# E3.net
KiCad netlist of a schematic drawn in Altium Designer
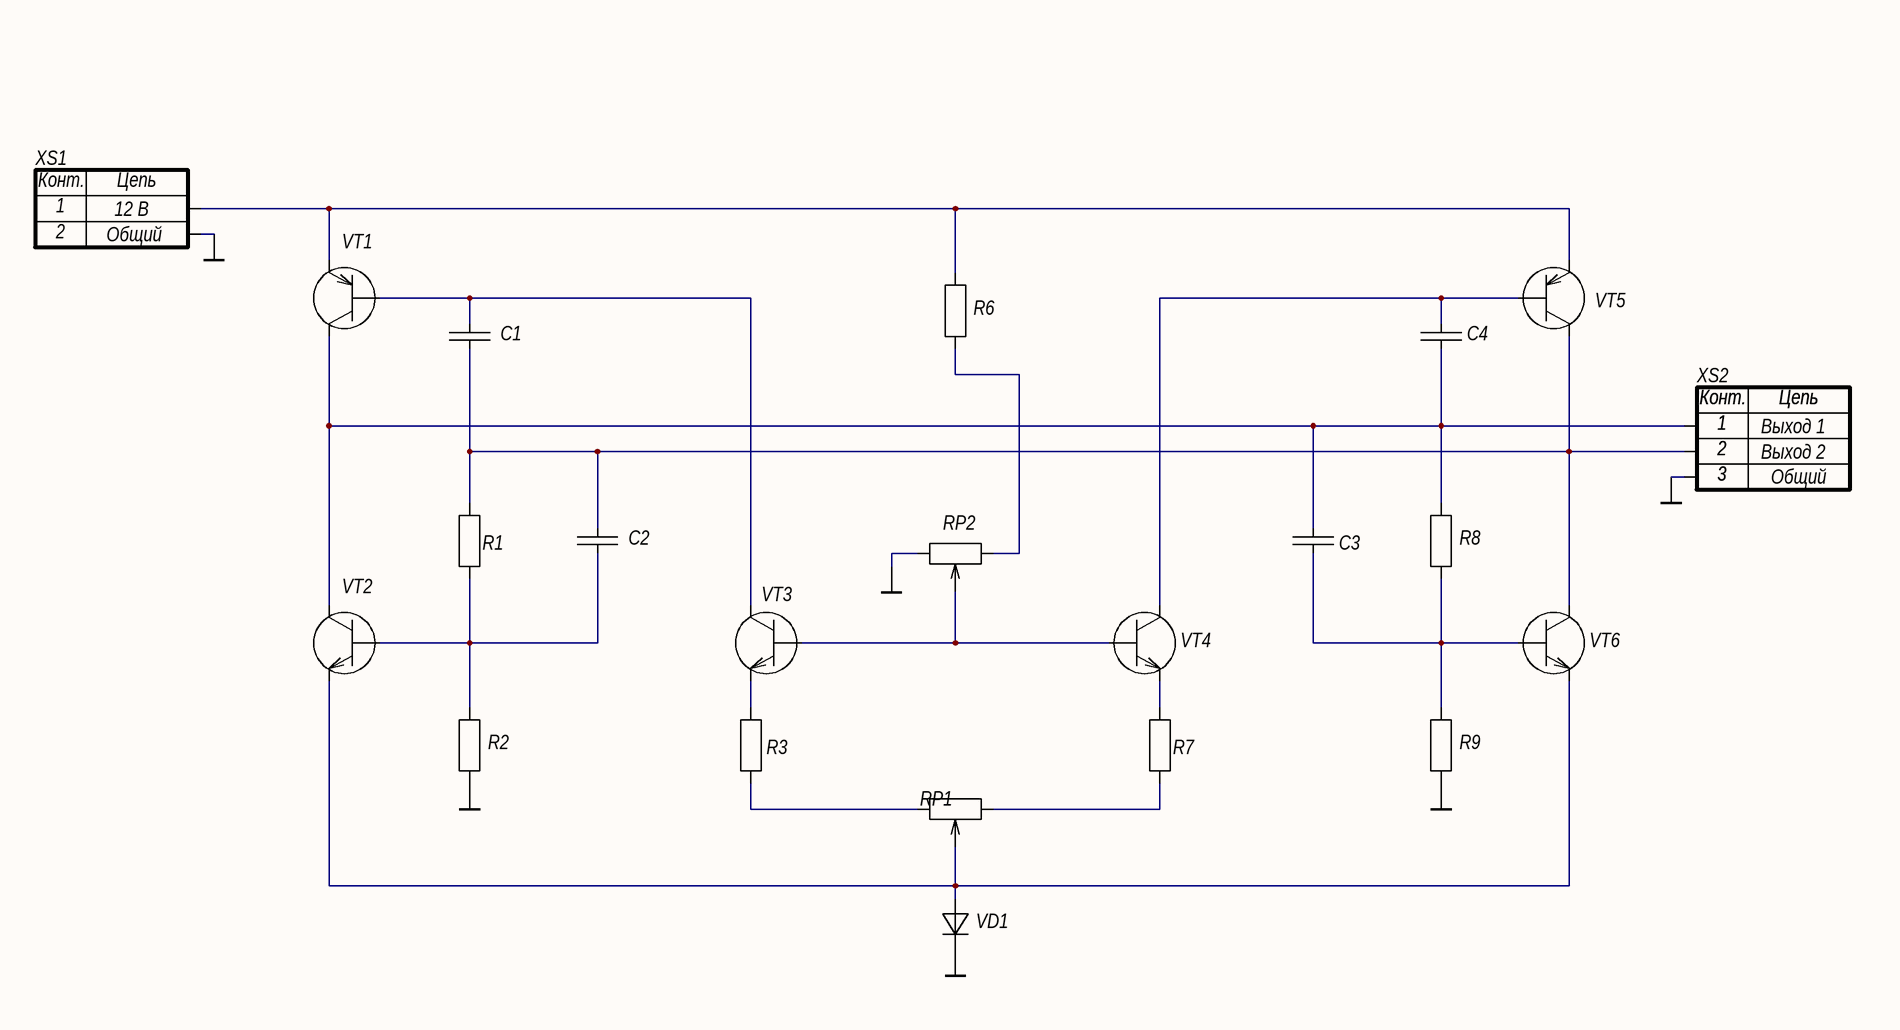
[diagram p0: E3.SchDoc, left]
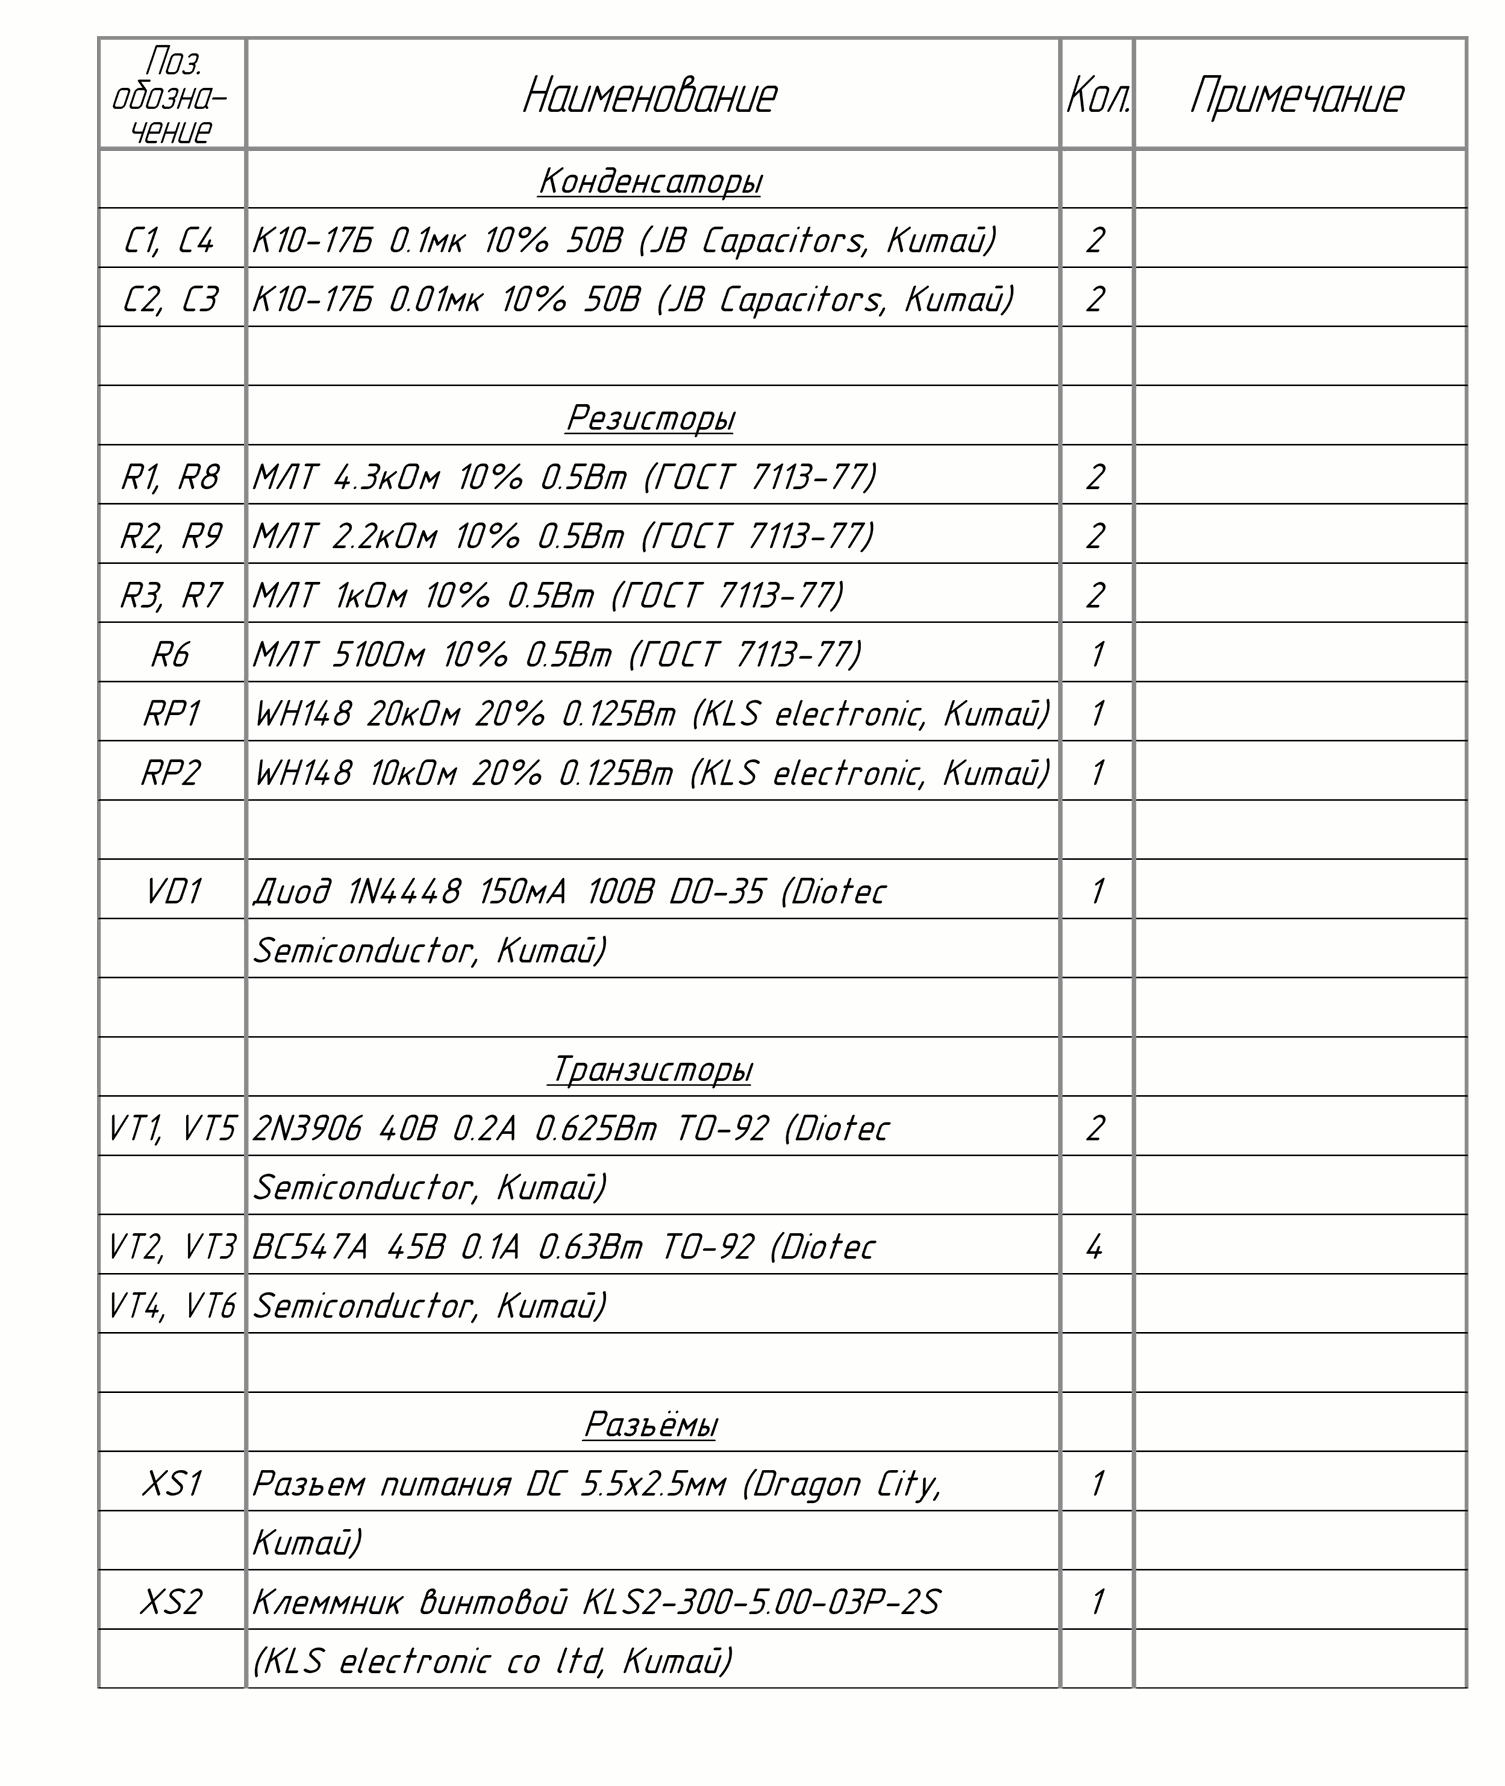
[diagram p1: E3.SchDoc, right]

(export (version "E")
  (design (tool "Eeschema 10.0.6"))
  (components
    (comp (ref "C1") (value "0,1мк") (footprint "PcbLib:C_THT_5mm") (libsource (lib "Schlib") (part "C")))
    (comp (ref "C2") (value "0,01мк") (footprint "PcbLib:C_THT_5mm") (libsource (lib "Schlib") (part "C")))
    (comp (ref "C3") (value "0,01мк") (footprint "PcbLib:C_THT_5mm") (libsource (lib "Schlib") (part "C")))
    (comp (ref "C4") (value "0,1мк") (footprint "PcbLib:C_THT_5mm") (libsource (lib "Schlib") (part "C")))
    (comp (ref "R1") (value "4,3к") (footprint "PcbLib:R_THT_10.8mm") (libsource (lib "Schlib") (part "R")))
    (comp (ref "R2") (value "2,2к") (footprint "PcbLib:R_THT_10.8mm") (libsource (lib "Schlib") (part "R")))
    (comp (ref "R3") (value "1к") (footprint "PcbLib:R_THT_10.8mm") (libsource (lib "Schlib") (part "R")))
    (comp (ref "R6") (value "510") (footprint "PcbLib:R_THT_10.8mm") (libsource (lib "Schlib") (part "R")))
    (comp (ref "R7") (value "1к") (footprint "PcbLib:R_THT_10.8mm") (libsource (lib "Schlib") (part "R")))
    (comp (ref "R8") (value "4,3к") (footprint "PcbLib:R_THT_10.8mm") (libsource (lib "Schlib") (part "R")))
    (comp (ref "R9") (value "2,2к") (footprint "PcbLib:R_THT_10.8mm") (libsource (lib "Schlib") (part "R")))
    (comp (ref "RP1")
      (value "20к")
      (footprint "PcbLib:Potentiometer")
      (libsource (lib "Schlib") (part "Potentiometer"))
    )
    (comp (ref "RP2")
      (value "10k")
      (footprint "PcbLib:Potentiometer")
      (libsource (lib "Schlib") (part "Potentiometer"))
    )
    (comp (ref "VD1") (value "VD") (footprint "PcbLib:Diode_THT") (libsource (lib "Schlib") (part "VD")))
    (comp (ref "VT1")
      (value "2N3906")
      (footprint "PcbLib:TO-92_EBC")
      (libsource (lib "Schlib") (part "VT_B_PNP"))
    )
    (comp (ref "VT2")
      (value "BC547A")
      (footprint "PcbLib:TO-92_CBE")
      (libsource (lib "Schlib") (part "VT_B_NPN"))
    )
    (comp (ref "VT3")
      (value "BC547A")
      (footprint "PcbLib:TO-92_CBE")
      (libsource (lib "Schlib") (part "VT_B_NPN"))
    )
    (comp (ref "VT4")
      (value "BC547A")
      (footprint "PcbLib:TO-92_CBE")
      (libsource (lib "Schlib") (part "VT_B_NPN"))
    )
    (comp (ref "VT5")
      (value "2N3906")
      (footprint "PcbLib:TO-92_EBC")
      (libsource (lib "Schlib") (part "VT_B_PNP"))
    )
    (comp (ref "VT6")
      (value "BC547A")
      (footprint "PcbLib:TO-92_CBE")
      (libsource (lib "Schlib") (part "VT_B_NPN"))
    )
    (comp (ref "XS1")
      (value "XS2_R")
      (footprint "PcbLib:XS2_Power")
      (libsource (lib "Schlib") (part "XS2_R"))
    )
    (comp (ref "XS2") (value "XS3_L") (footprint "PcbLib:XS3") (libsource (lib "Schlib") (part "XS3_L")))
  )
  (nets
    (net (code "1") (name "GND") (class "Default")
      (node (ref "R2") (pin "2") (pinfunction "2_2") (pintype "passive"))
      (node (ref "R9") (pin "2") (pinfunction "2_2") (pintype "passive"))
      (node (ref "RP2") (pin "1") (pinfunction "1_1") (pintype "passive"))
      (node (ref "VD1") (pin "2") (pinfunction "2_2") (pintype "passive"))
      (node (ref "XS1") (pin "2") (pinfunction "2_2") (pintype "passive"))
      (node (ref "XS2") (pin "3") (pinfunction "3_3") (pintype "passive"))
    )
    (net (code "2") (name "Net-(C1-Pad1)") (class "Default")
      (node (ref "C1") (pin "1") (pinfunction "1_1") (pintype "passive"))
      (node (ref "VT1") (pin "2") (pinfunction "2_2") (pintype "passive"))
      (node (ref "VT3") (pin "1") (pinfunction "1_1") (pintype "passive"))
    )
    (net (code "3") (name "Net-(C1-Pad2)") (class "Default")
      (node (ref "C1") (pin "2") (pinfunction "2_2") (pintype "passive"))
      (node (ref "C2") (pin "1") (pinfunction "1_1") (pintype "passive"))
      (node (ref "R1") (pin "1") (pinfunction "1_1") (pintype "passive"))
      (node (ref "VT5") (pin "1") (pinfunction "1_1") (pintype "passive"))
      (node (ref "VT6") (pin "1") (pinfunction "1_1") (pintype "passive"))
      (node (ref "XS2") (pin "2") (pinfunction "2_2") (pintype "passive"))
    )
    (net (code "4") (name "Net-(C2-Pad2)") (class "Default")
      (node (ref "C2") (pin "2") (pinfunction "2_2") (pintype "passive"))
      (node (ref "R1") (pin "2") (pinfunction "2_2") (pintype "passive"))
      (node (ref "R2") (pin "1") (pinfunction "1_1") (pintype "passive"))
      (node (ref "VT2") (pin "2") (pinfunction "2_2") (pintype "passive"))
    )
    (net (code "5") (name "Net-(C3-Pad1)") (class "Default")
      (node (ref "C3") (pin "1") (pinfunction "1_1") (pintype "passive"))
      (node (ref "C4") (pin "2") (pinfunction "2_2") (pintype "passive"))
      (node (ref "R8") (pin "1") (pinfunction "1_1") (pintype "passive"))
      (node (ref "VT1") (pin "1") (pinfunction "1_1") (pintype "passive"))
      (node (ref "VT2") (pin "1") (pinfunction "1_1") (pintype "passive"))
      (node (ref "XS2") (pin "1") (pinfunction "1_1") (pintype "passive"))
    )
    (net (code "6") (name "Net-(C3-Pad2)") (class "Default")
      (node (ref "C3") (pin "2") (pinfunction "2_2") (pintype "passive"))
      (node (ref "R8") (pin "2") (pinfunction "2_2") (pintype "passive"))
      (node (ref "R9") (pin "1") (pinfunction "1_1") (pintype "passive"))
      (node (ref "VT6") (pin "2") (pinfunction "2_2") (pintype "passive"))
    )
    (net (code "7") (name "Net-(C4-Pad1)") (class "Default")
      (node (ref "C4") (pin "1") (pinfunction "1_1") (pintype "passive"))
      (node (ref "VT4") (pin "1") (pinfunction "1_1") (pintype "passive"))
      (node (ref "VT5") (pin "2") (pinfunction "2_2") (pintype "passive"))
    )
    (net (code "8") (name "Net-(R3-Pad1)") (class "Default")
      (node (ref "R3") (pin "1") (pinfunction "1_1") (pintype "passive"))
      (node (ref "VT3") (pin "3") (pinfunction "3_3") (pintype "passive"))
    )
    (net (code "9") (name "Net-(R3-Pad2)") (class "Default")
      (node (ref "R3") (pin "2") (pinfunction "2_2") (pintype "passive"))
      (node (ref "RP1") (pin "1") (pinfunction "1_1") (pintype "passive"))
    )
    (net (code "10") (name "Net-(R6-Pad1)") (class "Default")
      (node (ref "R6") (pin "1") (pinfunction "1_1") (pintype "passive"))
      (node (ref "RP2") (pin "3") (pinfunction "3_3") (pintype "passive"))
    )
    (net (code "11") (name "Net-(R6-Pad2)") (class "Default")
      (node (ref "R6") (pin "2") (pinfunction "2_2") (pintype "passive"))
      (node (ref "VT1") (pin "3") (pinfunction "3_3") (pintype "passive"))
      (node (ref "VT5") (pin "3") (pinfunction "3_3") (pintype "passive"))
      (node (ref "XS1") (pin "1") (pinfunction "1_1") (pintype "passive"))
    )
    (net (code "12") (name "Net-(R7-Pad1)") (class "Default")
      (node (ref "R7") (pin "1") (pinfunction "1_1") (pintype "passive"))
      (node (ref "VT4") (pin "3") (pinfunction "3_3") (pintype "passive"))
    )
    (net (code "13") (name "Net-(R7-Pad2)") (class "Default")
      (node (ref "R7") (pin "2") (pinfunction "2_2") (pintype "passive"))
      (node (ref "RP1") (pin "3") (pinfunction "3_3") (pintype "passive"))
    )
    (net (code "14") (name "Net-(RP1-Pad2)") (class "Default")
      (node (ref "RP1") (pin "2") (pinfunction "2_2") (pintype "passive"))
      (node (ref "VD1") (pin "1") (pinfunction "1_1") (pintype "passive"))
      (node (ref "VT2") (pin "3") (pinfunction "3_3") (pintype "passive"))
      (node (ref "VT6") (pin "3") (pinfunction "3_3") (pintype "passive"))
    )
    (net (code "15") (name "Net-(RP2-Pad2)") (class "Default")
      (node (ref "RP2") (pin "2") (pinfunction "2_2") (pintype "passive"))
      (node (ref "VT3") (pin "2") (pinfunction "2_2") (pintype "passive"))
      (node (ref "VT4") (pin "2") (pinfunction "2_2") (pintype "passive"))
    )
  )
)
